# USBC_B.net
KiCad netlist of a schematic drawn in Altium Designer
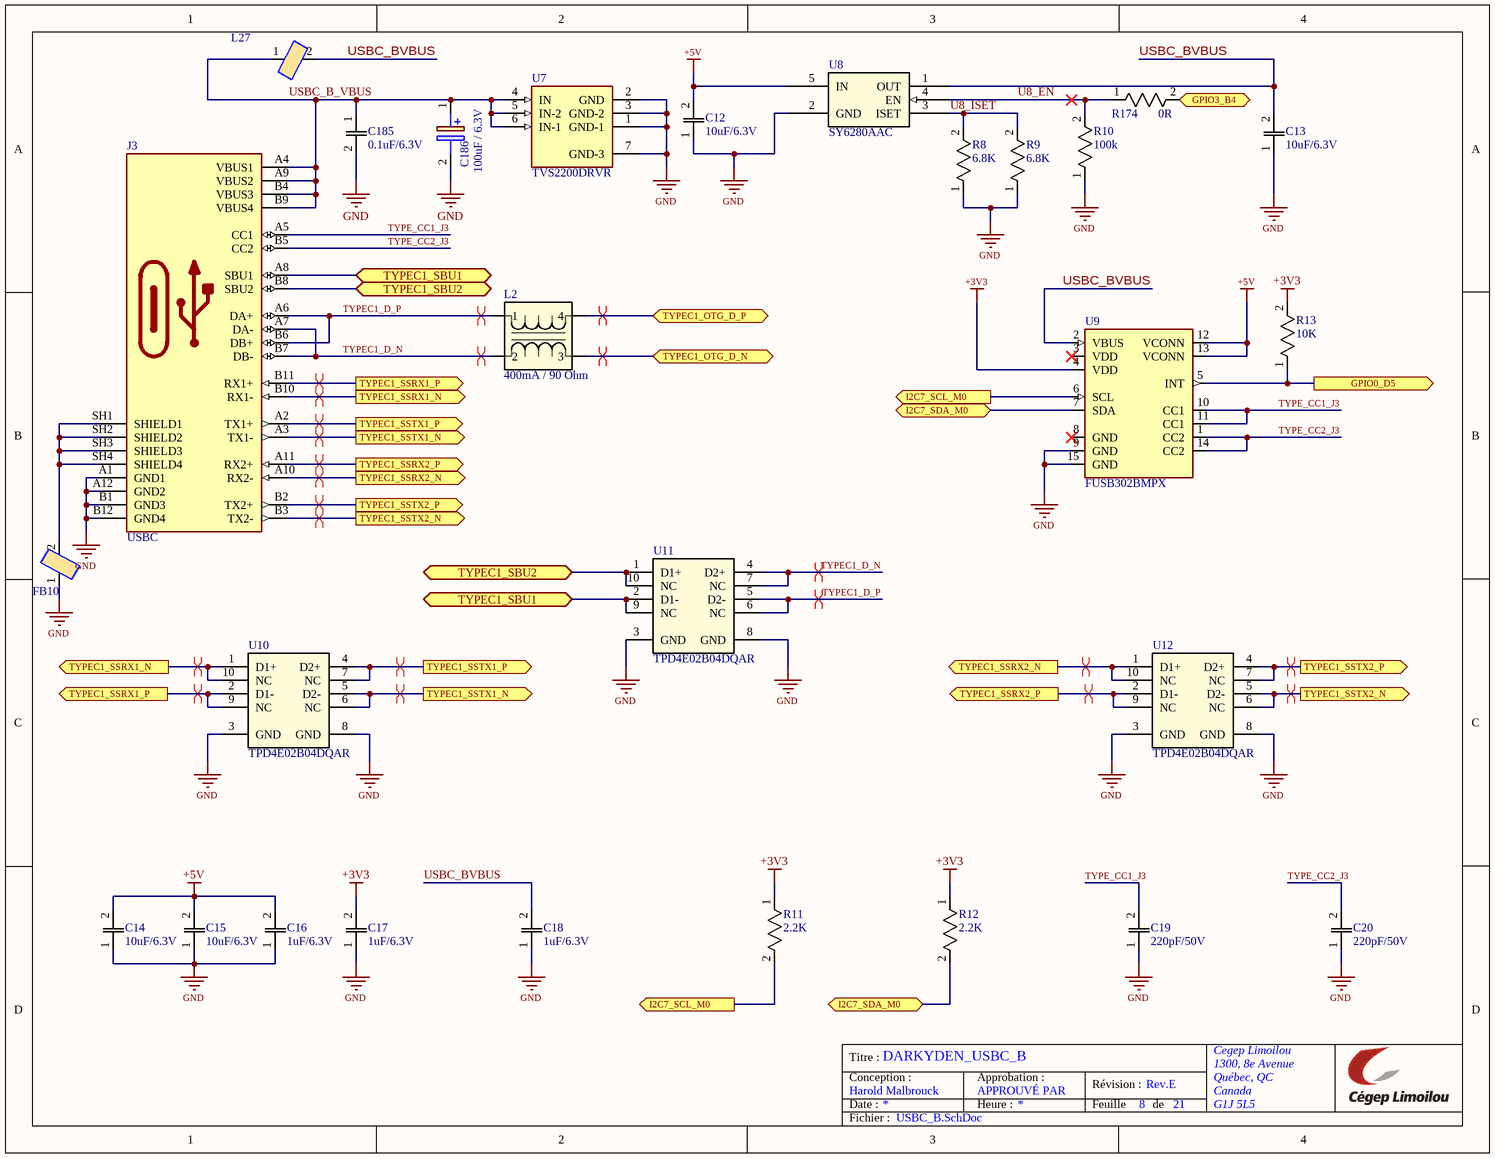
[diagram p0: USBC_B.SchDoc]

(export (version "E")
  (design (tool "Eeschema 10.0.6"))
  (components
    (comp (ref "C12")
      (value "10uF/6.3V")
      (footprint "C0805")
      (fields
        (field (name "MOUSER PART NUMBER") "80-C0805C106K9R")
        (field (name "ARROW PART NUMBER") "C0805C106K9RACTU")
        (field (name "MANUFACTURER") "KEMET")
      )
      (libsource (lib "DARKYDEN") (part "C0805C106K9RACTU"))
    )
    (comp (ref "C13")
      (value "10uF/6.3V")
      (footprint "C0805")
      (fields
        (field (name "MOUSER PART NUMBER") "80-C0805C106K9R")
        (field (name "ARROW PART NUMBER") "C0805C106K9RACTU")
        (field (name "MANUFACTURER") "KEMET")
      )
      (libsource (lib "DARKYDEN") (part "C0805C106K9RACTU"))
    )
    (comp (ref "C14")
      (value "10uF/6.3V")
      (footprint "C0805")
      (fields
        (field (name "MOUSER PART NUMBER") "80-C0805C106K9R")
        (field (name "ARROW PART NUMBER") "C0805C106K9RACTU")
        (field (name "MANUFACTURER") "KEMET")
      )
      (libsource (lib "DARKYDEN") (part "C0805C106K9RACTU"))
    )
    (comp (ref "C15")
      (value "10uF/6.3V")
      (footprint "C0805")
      (fields
        (field (name "MOUSER PART NUMBER") "80-C0805C106K9R")
        (field (name "ARROW PART NUMBER") "C0805C106K9RACTU")
        (field (name "MANUFACTURER") "KEMET")
      )
      (libsource (lib "DARKYDEN") (part "C0805C106K9RACTU"))
    )
    (comp (ref "C16")
      (value "1uF/6.3V")
      (footprint "C0805")
      (description "1 uF, 6.3 V, ± 10%, X7R, 0805 [2012 Metric] Multilayer Ceramic Capacitor,")
      (fields
        (field (name "MOUSER PART NUMBER") "80-C0805C105K9R")
        (field (name "ARROW PART NUMBER") "C0805C105K9RACTU")
      )
      (libsource (lib "DARKYDEN") (part "C0805C105K9RACTU"))
    )
    (comp (ref "C17")
      (value "1uF/6.3V")
      (footprint "C0805")
      (description "1 uF, 6.3 V, ± 10%, X7R, 0805 [2012 Metric] Multilayer Ceramic Capacitor,")
      (fields
        (field (name "MOUSER PART NUMBER") "80-C0805C105K9R")
        (field (name "ARROW PART NUMBER") "C0805C105K9RACTU")
      )
      (libsource (lib "DARKYDEN") (part "C0805C105K9RACTU"))
    )
    (comp (ref "C18")
      (value "1uF/6.3V")
      (footprint "C0805")
      (description "1 uF, 6.3 V, ± 10%, X7R, 0805 [2012 Metric] Multilayer Ceramic Capacitor,")
      (fields
        (field (name "MOUSER PART NUMBER") "80-C0805C105K9R")
        (field (name "ARROW PART NUMBER") "C0805C105K9RACTU")
      )
      (libsource (lib "DARKYDEN") (part "C0805C105K9RACTU"))
    )
    (comp (ref "C19")
      (value "220pF/50V")
      (footprint "C0805")
      (description "Cap Ceramic 220pF 50V X7R 20% Pad SMD 0805 125C T/R")
      (fields
        (field (name "MANUFACTURER") "KEMET")
        (field (name "MANUFACTURER PART NUMBER") "C0805C221M5RACTU")
      )
      (libsource (lib "DARKYDEN") (part "C0805C221M5RACTU"))
    )
    (comp (ref "C20")
      (value "220pF/50V")
      (footprint "C0805")
      (description "Cap Ceramic 220pF 50V X7R 20% Pad SMD 0805 125C T/R")
      (fields
        (field (name "MANUFACTURER") "KEMET")
        (field (name "MANUFACTURER PART NUMBER") "C0805C221M5RACTU")
      )
      (libsource (lib "DARKYDEN") (part "C0805C221M5RACTU"))
    )
    (comp (ref "C185")
      (value "0.1uF/6.3V")
      (footprint "C0805")
      (description "0.1uF 6.3V X7R 10% Pad SMD 0805 125C T/R")
      (fields
        (field (name "MOUSER PART NUMBER") "80-C0805C104K9R")
        (field (name "ARROW PART NUMBER") "C0805C104K9RACTU")
      )
      (libsource (lib "DARKYDEN") (part "C0805C104K9RACTU"))
    )
    (comp (ref "C186")
      (value "100uF / 6.3V")
      (footprint "SamacSys:EEE0GA101SR")
      (description "100uF 6.3V 20% Cap Aluminum Lytic  SMD 0.36 Ohm 240mA 2000h 105C Automotive T/R")
      (fields
        (field (name "MOUSER PART NUMBER") "667-EEE-FPJ101UAR")
        (field (name "ARROW PART NUMBER") "EEE-FPJ101UAR")
      )
      (libsource (lib "SamacSys") (part "EEE-FPJ101UAR"))
    )
    (comp (ref "FB10")
      (value "220R / 100MHz")
      (footprint "SamacSys:BLM18SP221SN1B")
      (description "Ferrite Beads Multi-Layer 220Ohm 25% 100MHz 2A 50mOhm DCR 0603 Paper T/R")
      (fields
        (field (name "MOUSER PART NUMBER") "81-BLM18EG221SN1D")
        (field (name "ARROW PART NUMBER") "BLM18EG221SN1D")
      )
      (libsource (lib "SamacSys") (part "BLM18EG221SN1D"))
    )
    (comp (ref "J3")
      (value "USBC")
      (footprint "USB_C")
      (fields (field (name "MF") "Molex") (field (name "MP") "2012670005"))
      (libsource (lib "DARKYDEN") (part "USBC"))
    )
    (comp (ref "L2")
      (value "400mA / 90 Ohm")
      (footprint "SamacSys:ACM20129002PT002")
      (description "Ferrite Beads Wirewound Common Mode Filter 90Ohm 100MHz 400mA 0805 T/R")
      (fields
        (field (name "MOUSER PART NUMBER") "810-ACM20129002PT002")
        (field (name "ARROW PART NUMBER") "ACM2012-900-2P-T002")
      )
      (libsource (lib "SamacSys") (part "ACM2012-900-2P-T002"))
    )
    (comp (ref "L27")
      (value "FBMJ2125HM210NT")
      (footprint "INDC2012X105N")
      (description "Ferrite Beads Power Chip 21Ohm 30% 100MHz 6A 0.004Ohm DCR 0805 Automotive T/R")
      (fields
        (field (name "MANUFACTURER") "Taiyo Yuden")
        (field (name "MOUSER PART NUMBER") "963-FBMJ2125HM210NT")
      )
      (libsource (lib "SamacSys") (part "FBMJ2125HM210NT"))
    )
    (comp (ref "R8")
      (value "6.8K")
      (footprint "SamacSys:RESC1608X55N")
      (description "6.8 kOhm, ± 5%, 100 mW, 0603 [1608 Metric], Thick Film, General Purpose")
      (fields (field (name "ARROW PART NUMBER") "ERJ-3GEYJ682V") (field (name "MANUFACTURER") "Panasonic"))
      (libsource (lib "DARKYDEN") (part "ERJ-3GEYJ682V"))
    )
    (comp (ref "R9")
      (value "6.8K")
      (footprint "SamacSys:RESC1608X55N")
      (description "6.8 kOhm, ± 5%, 100 mW, 0603 [1608 Metric], Thick Film, General Purpose")
      (fields (field (name "ARROW PART NUMBER") "ERJ-3GEYJ682V") (field (name "MANUFACTURER") "Panasonic"))
      (libsource (lib "DARKYDEN") (part "ERJ-3GEYJ682V"))
    )
    (comp (ref "R10")
      (value "100k")
      (footprint "SamacSys:RESC1608X55N")
      (description "100K Ohm 5%  Res Thick Film 0603 1/10W +/-200ppm/ßC Molded SMD Punched Carrier T/R")
      (fields
        (field (name "MOUSER PART NUMBER") "667-ERJ-3GEYJ104V")
        (field (name "ARROW PART NUMBER") "ERJ-3GEYJ104V")
      )
      (libsource (lib "DARKYDEN") (part "ERJ-3GEYJ104V"))
    )
    (comp (ref "R11")
      (value "2.2K")
      (footprint "SamacSys:RESC1608X55N")
      (description "2.2 kOhm, ï¿½ 5%, 100 mW, 0603 [1608 Metric], Thick Film, General Purpose")
      (fields
        (field (name "MOUSER PART NUMBER") "667-ERJ-3GEYJ222V")
        (field (name "ARROW PART NUMBER") "ERJ-3GEYJ222V")
      )
      (libsource (lib "DARKYDEN") (part "ERJ-3GEYJ222V"))
    )
    (comp (ref "R12")
      (value "2.2K")
      (footprint "SamacSys:RESC1608X55N")
      (description "2.2 kOhm, ï¿½ 5%, 100 mW, 0603 [1608 Metric], Thick Film, General Purpose")
      (fields
        (field (name "MOUSER PART NUMBER") "667-ERJ-3GEYJ222V")
        (field (name "ARROW PART NUMBER") "ERJ-3GEYJ222V")
      )
      (libsource (lib "DARKYDEN") (part "ERJ-3GEYJ222V"))
    )
    (comp (ref "R13")
      (value "10K")
      (footprint "SamacSys:RESC1608X55N")
      (description "10K Ohm 5% Res Thick Film 0603  0.1W(1/10W) ±200ppm/C Pad SMD Automotive T/R")
      (fields
        (field (name "MOUSER PART NUMBER") "667-ERJ-3GEYJ103V")
        (field (name "ARROW PART NUMBER") "ERJ-3GEYJ103V")
      )
      (libsource (lib "DARKYDEN") (part "ERJ-3GEYJ103V"))
    )
    (comp (ref "R174")
      (value "0R")
      (footprint "RESC1608X55N")
      (description "Zero Ohm Resistor, Jumper, 0603 [1608 Metric], Thick Film, 100 mW, 1 A, Surface Mount")
      (fields
        (field (name "MOUSER PART NUMBER") "667-ERJ-3GEY0R00V")
        (field (name "ARROW PART NUMBER") "ERJ-3GEY0R00V")
      )
      (libsource (lib "DARKYDEN") (part "ERJ-3GEY0R00V"))
    )
    (comp (ref "U7")
      (value "TVS2200DRVR")
      (footprint "SON65P200X200X80-7N")
      (description "ESD Suppressors / TVS Diodes 22V flat-clamp surge protection device 6-WSON -40 to 125")
      (fields (field (name "MF") "Texas Instruments"))
      (libsource (lib "TVS2200") (part "TVS2200DRVR"))
    )
    (comp (ref "U8")
      (value "SY6280AAC")
      (footprint "SamacSys:SOT95P285X140-5N")
      (description "2.4V~5.5V 80mΩ Active High 1 High-side switch SOT-23-5 Power Distribution Switches ROHS")
      (libsource (lib "SamacSys") (part "SY6280AAC"))
    )
    (comp (ref "U9")
      (value "FUSB302BMPX")
      (footprint "SamacSys:QFN50P250X250X80-15N")
      (description "USB Controller USB 3.1 USB Interface 14-MLP (2.5x2.5)")
      (fields (field (name "MOUSER PART NUMBER") "512-FUSB302BMPX"))
      (libsource (lib "SamacSys") (part "FUSB302BMPX"))
    )
    (comp (ref "U10")
      (value "TPD4E02B04DQAR")
      (footprint "DQA0010A")
      (description "TVS DIODE 3.6V 8.8V 10USON / 4-Channel ESD Protection Diode for USB Type-C and HDMI 2.0")
      (fields (field (name "MANUFACTURER") "Texas Instruments"))
      (libsource (lib "TPD4E02B04DQAR") (part "TPD4E02B04DQAR"))
    )
    (comp (ref "U11")
      (value "TPD4E02B04DQAR")
      (footprint "DQA0010A")
      (description "TVS DIODE 3.6V 8.8V 10USON / 4-Channel ESD Protection Diode for USB Type-C and HDMI 2.0")
      (fields (field (name "MANUFACTURER") "Texas Instruments"))
      (libsource (lib "TPD4E02B04DQAR") (part "TPD4E02B04DQAR"))
    )
    (comp (ref "U12")
      (value "TPD4E02B04DQAR")
      (footprint "DQA0010A")
      (description "TVS DIODE 3.6V 8.8V 10USON / 4-Channel ESD Protection Diode for USB Type-C and HDMI 2.0")
      (fields (field (name "MANUFACTURER") "Texas Instruments"))
      (libsource (lib "TPD4E02B04DQAR") (part "TPD4E02B04DQAR"))
    )
  )
  (nets
    (net (code "1") (name "+3V3") (class "Default")
      (node (ref "C17") (pin "2") (pinfunction "2_2") (pintype "passive"))
      (node (ref "R11") (pin "1") (pinfunction "1_1") (pintype "passive"))
      (node (ref "R12") (pin "1") (pinfunction "1_1") (pintype "passive"))
      (node (ref "R13") (pin "2") (pinfunction "2_2") (pintype "passive"))
      (node (ref "U9") (pin "4") (pinfunction "VDD_4") (pintype "power_in"))
    )
    (net (code "2") (name "+5V") (class "Default")
      (node (ref "C12") (pin "2") (pinfunction "2_2") (pintype "passive"))
      (node (ref "C14") (pin "2") (pinfunction "2_2") (pintype "passive"))
      (node (ref "C15") (pin "2") (pinfunction "2_2") (pintype "passive"))
      (node (ref "C16") (pin "2") (pinfunction "2_2") (pintype "passive"))
      (node (ref "U8") (pin "5") (pinfunction "IN_5") (pintype "power_in"))
      (node (ref "U9") (pin "12") (pinfunction "VCONN_12") (pintype "power_in"))
      (node (ref "U9") (pin "13") (pinfunction "VCONN_13") (pintype "power_in"))
    )
    (net (code "3") (name "/GPIO0_D5") (class "Default")
      (node (ref "R13") (pin "1") (pinfunction "1_1") (pintype "passive"))
      (node (ref "U9") (pin "5") (pinfunction "INT_5") (pintype "output"))
    )
    (net (code "4") (name "/GPIO3_B4") (class "Default")
      (node (ref "R174") (pin "2") (pinfunction "2_2") (pintype "passive"))
    )
    (net (code "5") (name "/I2C7_SCL_M0") (class "Default")
      (node (ref "R11") (pin "2") (pinfunction "2_2") (pintype "passive"))
      (node (ref "U9") (pin "6") (pinfunction "SCL_6") (pintype "input"))
    )
    (net (code "6") (name "/I2C7_SDA_M0") (class "Default")
      (node (ref "R12") (pin "2") (pinfunction "2_2") (pintype "passive"))
      (node (ref "U9") (pin "7") (pinfunction "SDA_7") (pintype "bidirectional"))
    )
    (net (code "7") (name "/TYPEC1_D_N") (class "Default")
      (node (ref "J3") (pin "A7") (pinfunction "DA-_A7") (pintype "bidirectional"))
      (node (ref "J3") (pin "B7") (pinfunction "DB-_B7") (pintype "bidirectional"))
      (node (ref "L2") (pin "2") (pinfunction "2_2") (pintype "passive"))
      (node (ref "U11") (pin "4") (pinfunction "D2+_4") (pintype "passive"))
      (node (ref "U11") (pin "7") (pinfunction "NC_7") (pintype "passive"))
    )
    (net (code "8") (name "/TYPEC1_D_P") (class "Default")
      (node (ref "J3") (pin "A6") (pinfunction "DA+_A6") (pintype "bidirectional"))
      (node (ref "J3") (pin "B6") (pinfunction "DB+_B6") (pintype "bidirectional"))
      (node (ref "L2") (pin "1") (pinfunction "1_1") (pintype "passive"))
      (node (ref "U11") (pin "5") (pinfunction "D2-_5") (pintype "passive"))
      (node (ref "U11") (pin "6") (pinfunction "NC_6") (pintype "passive"))
    )
    (net (code "9") (name "/TYPEC1_OTG_D_N") (class "Default")
      (node (ref "L2") (pin "3") (pinfunction "3_3") (pintype "passive"))
    )
    (net (code "10") (name "/TYPEC1_OTG_D_P") (class "Default")
      (node (ref "L2") (pin "4") (pinfunction "4_4") (pintype "passive"))
    )
    (net (code "11") (name "/TYPEC1_SBU1") (class "Default")
      (node (ref "J3") (pin "A8") (pinfunction "SBU1_A8") (pintype "bidirectional"))
      (node (ref "U11") (pin "2") (pinfunction "D1-_2") (pintype "passive"))
      (node (ref "U11") (pin "9") (pinfunction "NC_9") (pintype "passive"))
    )
    (net (code "12") (name "/TYPEC1_SBU2") (class "Default")
      (node (ref "J3") (pin "B8") (pinfunction "SBU2_B8") (pintype "bidirectional"))
      (node (ref "U11") (pin "1") (pinfunction "D1+_1") (pintype "passive"))
      (node (ref "U11") (pin "10") (pinfunction "NC_10") (pintype "passive"))
    )
    (net (code "13") (name "/TYPEC1_SSRX1_N") (class "Default")
      (node (ref "J3") (pin "B10") (pinfunction "RX1-_B10") (pintype "input"))
      (node (ref "U10") (pin "1") (pinfunction "D1+_1") (pintype "passive"))
      (node (ref "U10") (pin "10") (pinfunction "NC_10") (pintype "passive"))
    )
    (net (code "14") (name "/TYPEC1_SSRX1_P") (class "Default")
      (node (ref "J3") (pin "B11") (pinfunction "RX1+_B11") (pintype "input"))
      (node (ref "U10") (pin "2") (pinfunction "D1-_2") (pintype "passive"))
      (node (ref "U10") (pin "9") (pinfunction "NC_9") (pintype "passive"))
    )
    (net (code "15") (name "/TYPEC1_SSRX2_N") (class "Default")
      (node (ref "J3") (pin "A10") (pinfunction "RX2-_A10") (pintype "input"))
      (node (ref "U12") (pin "1") (pinfunction "D1+_1") (pintype "passive"))
      (node (ref "U12") (pin "10") (pinfunction "NC_10") (pintype "passive"))
    )
    (net (code "16") (name "/TYPEC1_SSRX2_P") (class "Default")
      (node (ref "J3") (pin "A11") (pinfunction "RX2+_A11") (pintype "input"))
      (node (ref "U12") (pin "2") (pinfunction "D1-_2") (pintype "passive"))
      (node (ref "U12") (pin "9") (pinfunction "NC_9") (pintype "passive"))
    )
    (net (code "17") (name "/TYPEC1_SSTX1_N") (class "Default")
      (node (ref "J3") (pin "A3") (pinfunction "TX1-_A3") (pintype "output"))
      (node (ref "U10") (pin "5") (pinfunction "D2-_5") (pintype "passive"))
      (node (ref "U10") (pin "6") (pinfunction "NC_6") (pintype "passive"))
    )
    (net (code "18") (name "/TYPEC1_SSTX1_P") (class "Default")
      (node (ref "J3") (pin "A2") (pinfunction "TX1+_A2") (pintype "output"))
      (node (ref "U10") (pin "4") (pinfunction "D2+_4") (pintype "passive"))
      (node (ref "U10") (pin "7") (pinfunction "NC_7") (pintype "passive"))
    )
    (net (code "19") (name "/TYPEC1_SSTX2_N") (class "Default")
      (node (ref "J3") (pin "B3") (pinfunction "TX2-_B3") (pintype "output"))
      (node (ref "U12") (pin "5") (pinfunction "D2-_5") (pintype "passive"))
      (node (ref "U12") (pin "6") (pinfunction "NC_6") (pintype "passive"))
    )
    (net (code "20") (name "/TYPEC1_SSTX2_P") (class "Default")
      (node (ref "J3") (pin "B2") (pinfunction "TX2+_B2") (pintype "output"))
      (node (ref "U12") (pin "4") (pinfunction "D2+_4") (pintype "passive"))
      (node (ref "U12") (pin "7") (pinfunction "NC_7") (pintype "passive"))
    )
    (net (code "21") (name "/TYPE_CC1_J3") (class "Default")
      (node (ref "C19") (pin "2") (pinfunction "2_2") (pintype "passive"))
      (node (ref "J3") (pin "A5") (pinfunction "CC1_A5") (pintype "bidirectional"))
      (node (ref "U9") (pin "10") (pinfunction "CC1_10") (pintype "bidirectional"))
      (node (ref "U9") (pin "11") (pinfunction "CC1_11") (pintype "bidirectional"))
    )
    (net (code "22") (name "/TYPE_CC2_J3") (class "Default")
      (node (ref "C20") (pin "2") (pinfunction "2_2") (pintype "passive"))
      (node (ref "J3") (pin "B5") (pinfunction "CC2_B5") (pintype "bidirectional"))
      (node (ref "U9") (pin "1") (pinfunction "CC2_1") (pintype "bidirectional"))
      (node (ref "U9") (pin "14") (pinfunction "CC2_14") (pintype "bidirectional"))
    )
    (net (code "23") (name "/U8_EN") (class "Default")
      (node (ref "R10") (pin "2") (pinfunction "2_2") (pintype "passive"))
      (node (ref "R174") (pin "1") (pinfunction "1_1") (pintype "passive"))
      (node (ref "U8") (pin "4") (pinfunction "EN_4") (pintype "input"))
    )
    (net (code "24") (name "/U8_ISET") (class "Default")
      (node (ref "R8") (pin "2") (pinfunction "2_2") (pintype "passive"))
      (node (ref "R9") (pin "2") (pinfunction "2_2") (pintype "passive"))
      (node (ref "U8") (pin "3") (pinfunction "ISET_3") (pintype "passive"))
    )
    (net (code "25") (name "/USBC_BVBUS") (class "Default")
      (node (ref "C13") (pin "2") (pinfunction "2_2") (pintype "passive"))
      (node (ref "C18") (pin "2") (pinfunction "2_2") (pintype "passive"))
      (node (ref "L27") (pin "2") (pinfunction "2_2") (pintype "passive"))
      (node (ref "U8") (pin "1") (pinfunction "OUT_1") (pintype "power_in"))
      (node (ref "U9") (pin "2") (pinfunction "VBUS_2") (pintype "input"))
    )
    (net (code "26") (name "/USBC_B_VBUS") (class "Default")
      (node (ref "C185") (pin "1") (pinfunction "1_1") (pintype "passive"))
      (node (ref "C186") (pin "1") (pinfunction "+_1") (pintype "passive"))
      (node (ref "J3") (pin "A4") (pinfunction "VBUS1_A4") (pintype "power_in"))
      (node (ref "J3") (pin "A9") (pinfunction "VBUS2_A9") (pintype "power_in"))
      (node (ref "J3") (pin "B4") (pinfunction "VBUS3_B4") (pintype "power_in"))
      (node (ref "J3") (pin "B9") (pinfunction "VBUS4_B9") (pintype "power_in"))
      (node (ref "L27") (pin "1") (pinfunction "1_1") (pintype "passive"))
      (node (ref "U7") (pin "4") (pinfunction "IN_4") (pintype "input"))
      (node (ref "U7") (pin "5") (pinfunction "IN-2_5") (pintype "input"))
      (node (ref "U7") (pin "6") (pinfunction "IN-1_6") (pintype "input"))
    )
    (net (code "27") (name "GND") (class "Default")
      (node (ref "C12") (pin "1") (pinfunction "1_1") (pintype "passive"))
      (node (ref "C13") (pin "1") (pinfunction "1_1") (pintype "passive"))
      (node (ref "C14") (pin "1") (pinfunction "1_1") (pintype "passive"))
      (node (ref "C15") (pin "1") (pinfunction "1_1") (pintype "passive"))
      (node (ref "C16") (pin "1") (pinfunction "1_1") (pintype "passive"))
      (node (ref "C17") (pin "1") (pinfunction "1_1") (pintype "passive"))
      (node (ref "C18") (pin "1") (pinfunction "1_1") (pintype "passive"))
      (node (ref "C185") (pin "2") (pinfunction "2_2") (pintype "passive"))
      (node (ref "C186") (pin "2") (pinfunction "-_2") (pintype "passive"))
      (node (ref "C19") (pin "1") (pinfunction "1_1") (pintype "passive"))
      (node (ref "C20") (pin "1") (pinfunction "1_1") (pintype "passive"))
      (node (ref "FB10") (pin "1") (pinfunction "1_1") (pintype "passive"))
      (node (ref "J3") (pin "A1") (pinfunction "GND1_A1") (pintype "passive"))
      (node (ref "J3") (pin "A12") (pinfunction "GND2_A12") (pintype "passive"))
      (node (ref "J3") (pin "B1") (pinfunction "GND3_B1") (pintype "passive"))
      (node (ref "J3") (pin "B12") (pinfunction "GND4_B12") (pintype "passive"))
      (node (ref "R10") (pin "1") (pinfunction "1_1") (pintype "passive"))
      (node (ref "R8") (pin "1") (pinfunction "1_1") (pintype "passive"))
      (node (ref "R9") (pin "1") (pinfunction "1_1") (pintype "passive"))
      (node (ref "U10") (pin "3") (pinfunction "GND_3") (pintype "passive"))
      (node (ref "U10") (pin "8") (pinfunction "GND_8") (pintype "passive"))
      (node (ref "U11") (pin "3") (pinfunction "GND_3") (pintype "passive"))
      (node (ref "U11") (pin "8") (pinfunction "GND_8") (pintype "passive"))
      (node (ref "U12") (pin "3") (pinfunction "GND_3") (pintype "passive"))
      (node (ref "U12") (pin "8") (pinfunction "GND_8") (pintype "passive"))
      (node (ref "U7") (pin "1") (pinfunction "GND-1_1") (pintype "passive"))
      (node (ref "U7") (pin "2") (pinfunction "GND_2") (pintype "passive"))
      (node (ref "U7") (pin "3") (pinfunction "GND-2_3") (pintype "passive"))
      (node (ref "U7") (pin "7") (pinfunction "GND-3_7") (pintype "passive"))
      (node (ref "U8") (pin "2") (pinfunction "GND_2") (pintype "passive"))
      (node (ref "U9") (pin "15") (pinfunction "GND_15") (pintype "passive"))
      (node (ref "U9") (pin "9") (pinfunction "GND_9") (pintype "passive"))
    )
    (net (code "28") (name "Net-(J3-SHIELD1)") (class "Default")
      (node (ref "FB10") (pin "2") (pinfunction "2_2") (pintype "passive"))
      (node (ref "J3") (pin "SH1") (pinfunction "SHIELD1_SH1") (pintype "passive"))
      (node (ref "J3") (pin "SH2") (pinfunction "SHIELD2_SH2") (pintype "passive"))
      (node (ref "J3") (pin "SH3") (pinfunction "SHIELD3_SH3") (pintype "passive"))
      (node (ref "J3") (pin "SH4") (pinfunction "SHIELD4_SH4") (pintype "passive"))
    )
    (net (code "29") (name "unconnected-(U9-GND-Pad8)") (class "Default")
      (node (ref "U9") (pin "8") (pinfunction "GND_8") (pintype "passive+no_connect"))
    )
    (net (code "30") (name "unconnected-(U9-VDD-Pad3)") (class "Default")
      (node (ref "U9") (pin "3") (pinfunction "VDD_3") (pintype "power_in+no_connect"))
    )
  )
)
